# STM32LoRa.net
KiCad netlist of a schematic drawn in EAGLE
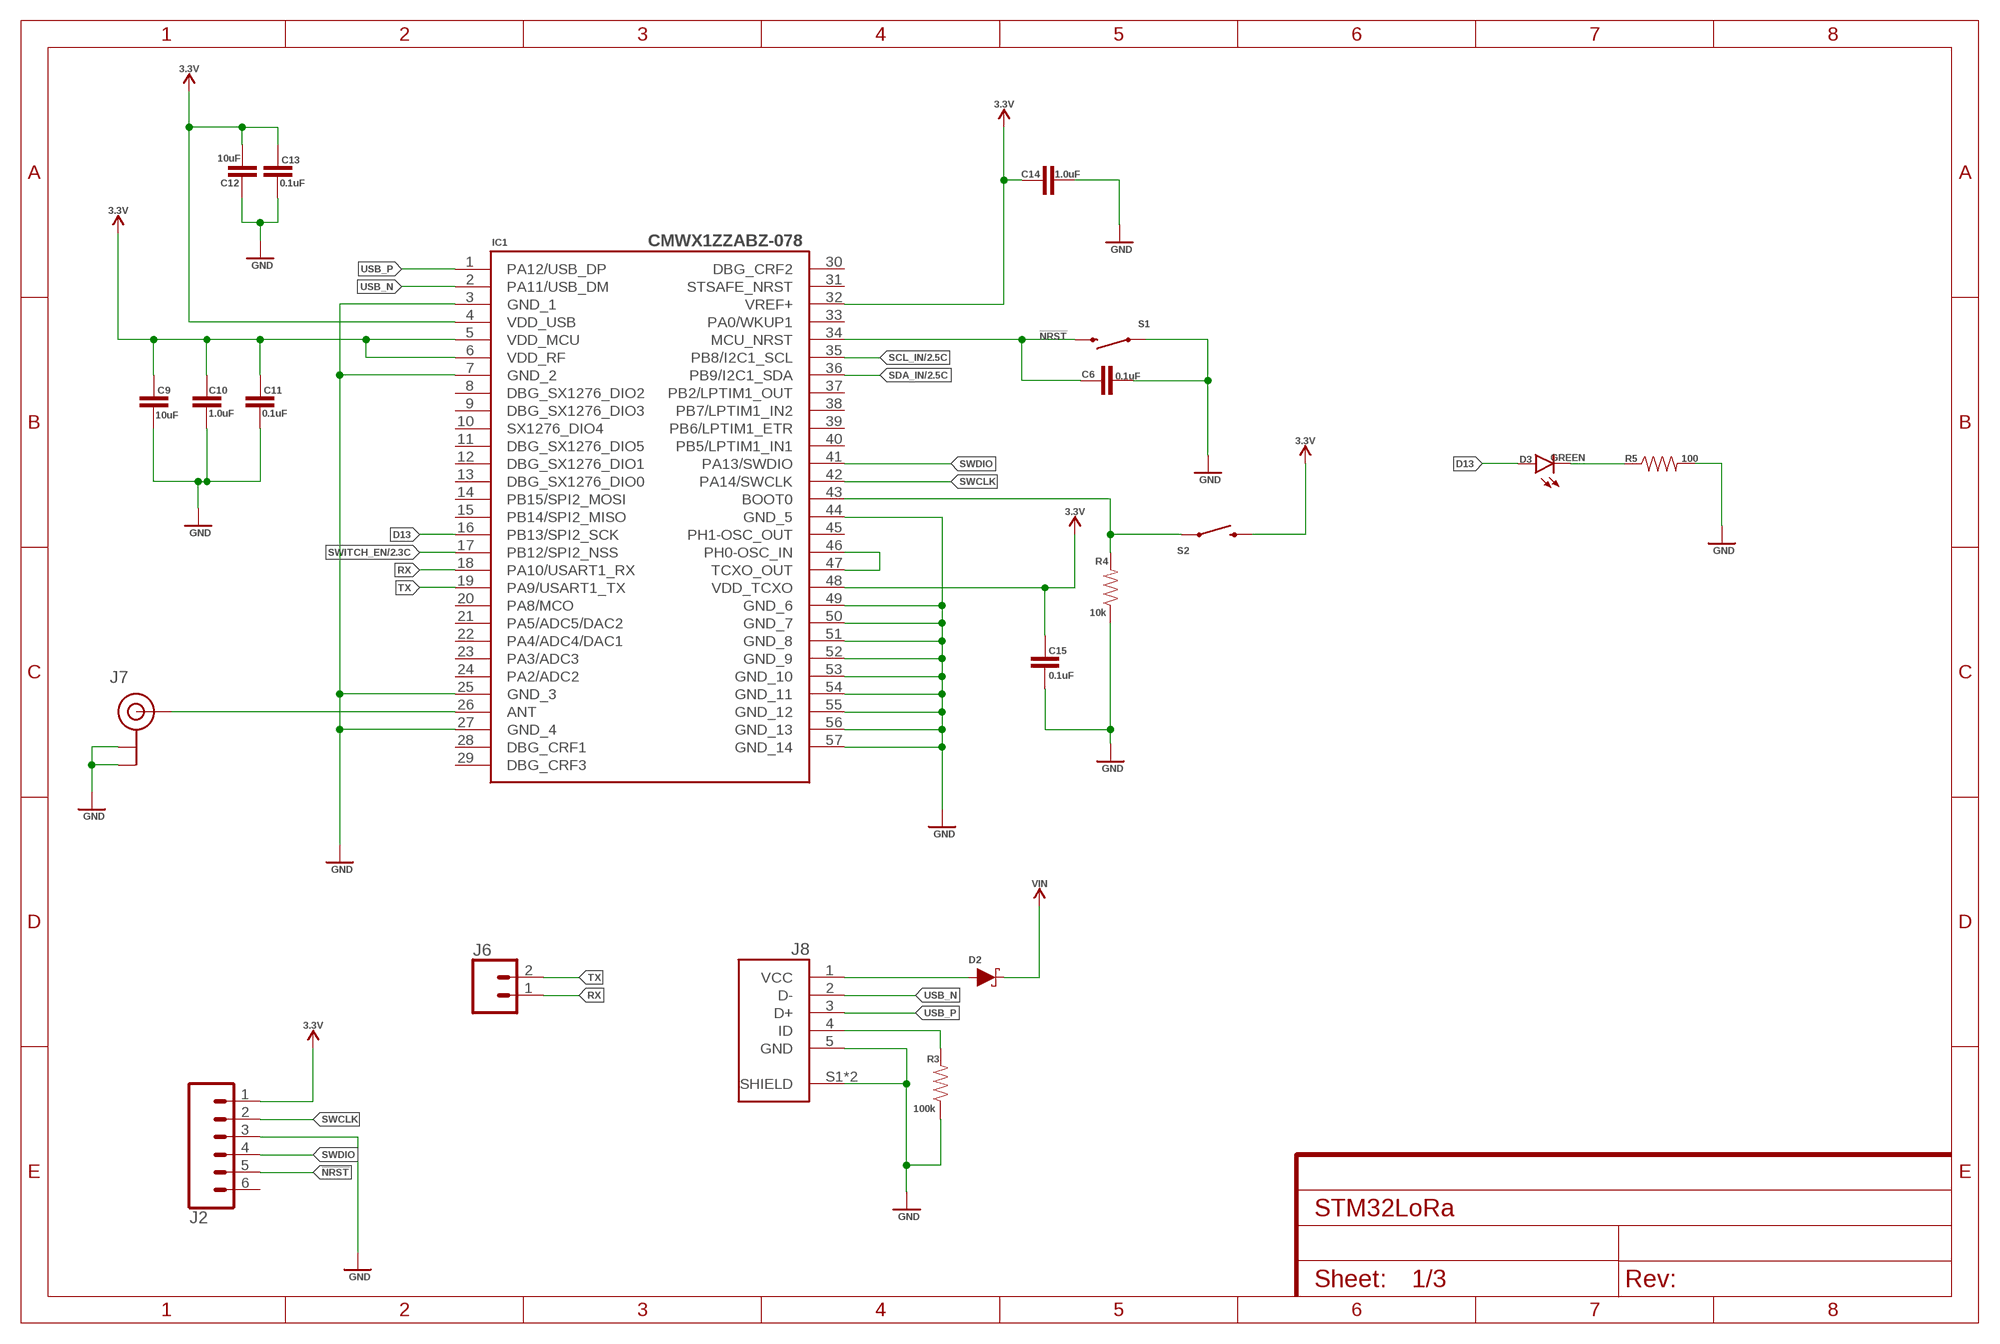
[diagram p0: schematic, sheet 1]
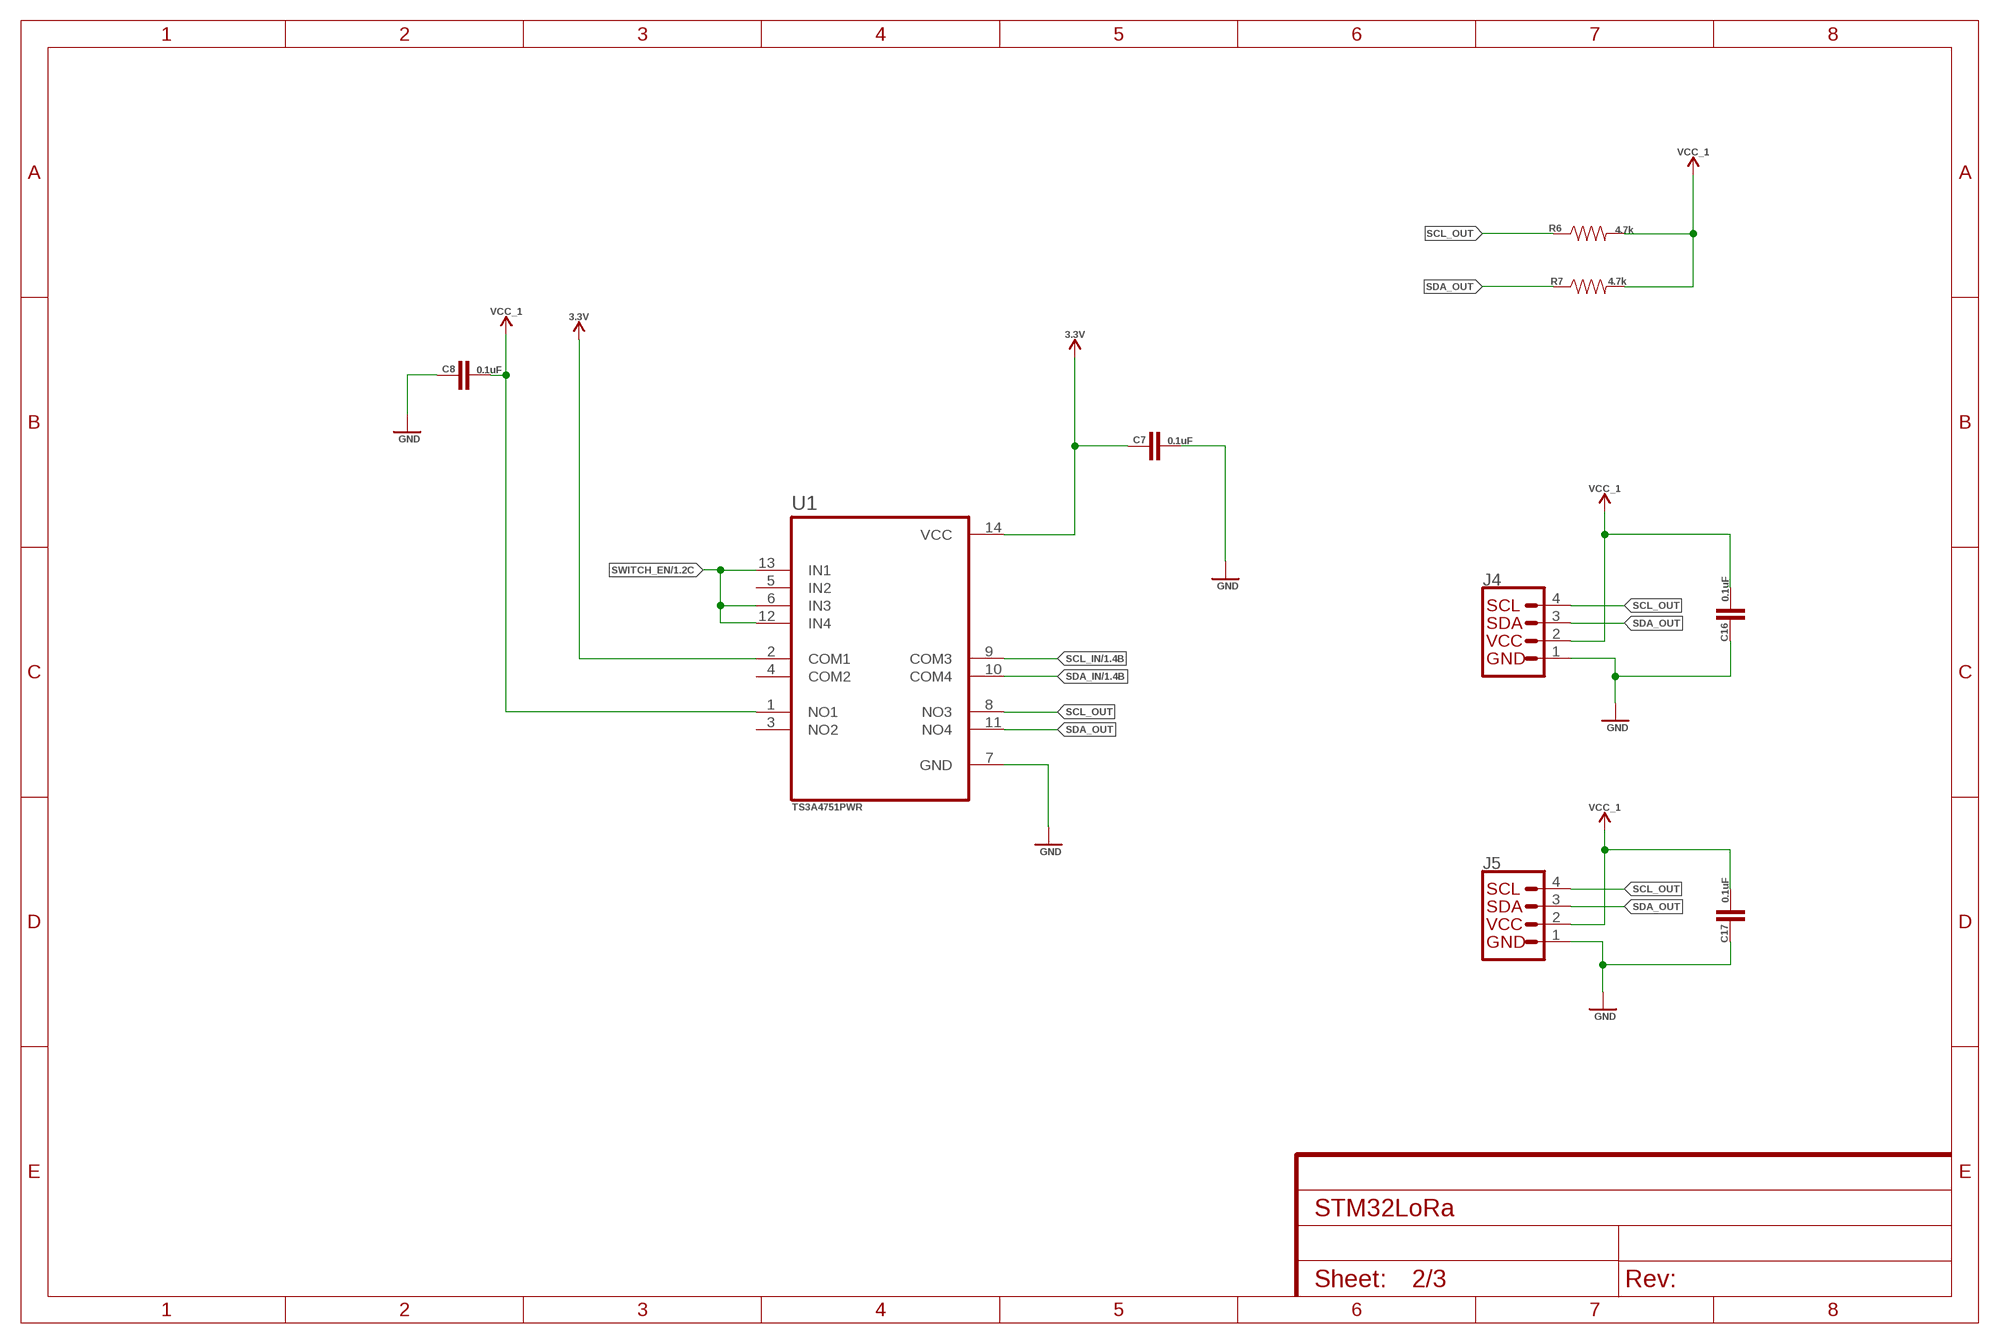
[diagram p1: schematic, sheet 2]
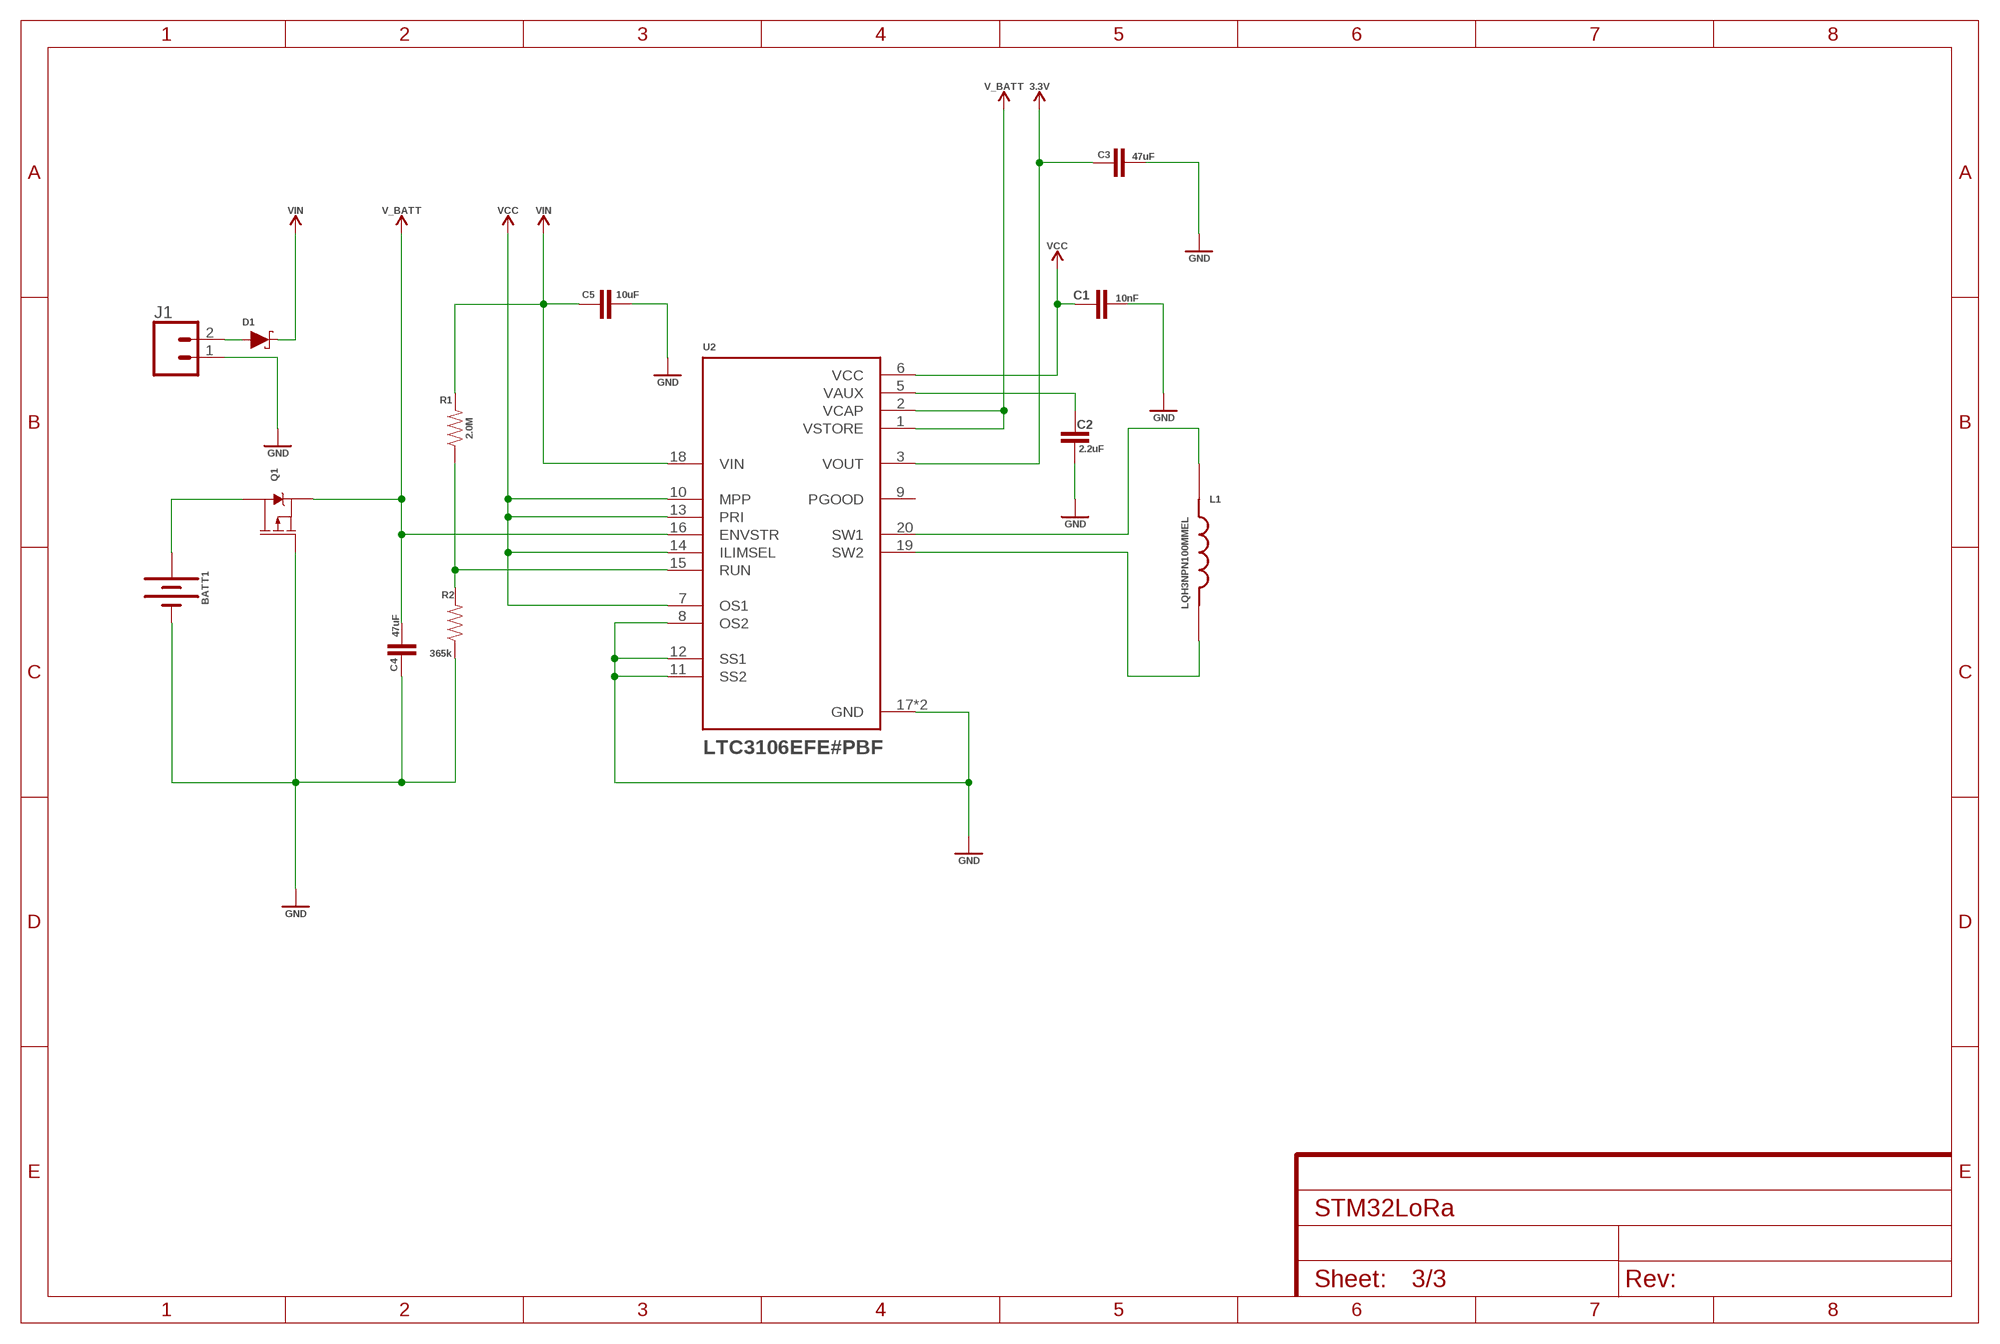
[diagram p2: schematic, sheet 3]

(export (version "E")
  (design (tool "Eeschema 10.0.6"))
  (components
    (comp (ref "C7")
      (value "0.1uF")
      (footprint "eagle-import:0603")
      (libsource (lib "eagle-import") (part "0.1UF-0603-25V-(+80/-20%)"))
    )
    (comp (ref "C8")
      (value "0.1uF")
      (footprint "eagle-import:0603")
      (libsource (lib "eagle-import") (part "0.1UF-0603-25V-(+80/-20%)"))
    )
    (comp (ref "C16")
      (value "0.1uF")
      (footprint "eagle-import:0603")
      (libsource (lib "eagle-import") (part "0.1UF-0603-25V-(+80/-20%)"))
    )
    (comp (ref "C17")
      (value "0.1uF")
      (footprint "eagle-import:0603")
      (libsource (lib "eagle-import") (part "0.1UF-0603-25V-(+80/-20%)"))
    )
    (comp (ref "J4")
      (value "Qwiic Right Angle")
      (footprint "eagle-import:1X04_1MM_RA")
      (libsource (lib "eagle-import") (part "I2C_STANDARDQWIIC"))
    )
    (comp (ref "J5")
      (value "I2C_STANDARD")
      (footprint "eagle-import:1X04")
      (libsource (lib "eagle-import") (part "I2C_STANDARD"))
    )
    (comp (ref "R6")
      (value "4.7k")
      (footprint "eagle-import:0603")
      (libsource (lib "eagle-import") (part "4.7KOHM-0603-1/10W-1%"))
    )
    (comp (ref "R7")
      (value "4.7k")
      (footprint "eagle-import:0603")
      (libsource (lib "eagle-import") (part "4.7KOHM-0603-1/10W-1%"))
    )
    (comp (ref "U1")
      (value "TS3A4751PWR")
      (footprint "eagle-import:SOP65P640X120-14N")
      (fields (field (name "DIGI-KEY_PART_NUMBER") "296-20700-1-ND") (field (name "MF") "Texas Instruments"))
      (libsource (lib "eagle-import") (part "TS3A4751PWR"))
    )
    (comp (ref "C6")
      (value "0.1uF")
      (footprint "eagle-import:0603")
      (libsource (lib "eagle-import") (part "0.1UF-0603-25V-(+80/-20%)"))
    )
    (comp (ref "C9")
      (value "10uF")
      (footprint "eagle-import:0603")
      (libsource (lib "eagle-import") (part "10UF-0603-6.3V-20%"))
    )
    (comp (ref "C10")
      (value "1.0uF")
      (footprint "eagle-import:0603")
      (libsource (lib "eagle-import") (part "1.0UF-0603-16V-10%"))
    )
    (comp (ref "C11")
      (value "0.1uF")
      (footprint "eagle-import:0603")
      (libsource (lib "eagle-import") (part "0.1UF-0603-25V-(+80/-20%)"))
    )
    (comp (ref "C12")
      (value "10uF")
      (footprint "eagle-import:0603")
      (libsource (lib "eagle-import") (part "10UF-0603-6.3V-20%"))
    )
    (comp (ref "C13")
      (value "0.1uF")
      (footprint "eagle-import:0603")
      (libsource (lib "eagle-import") (part "0.1UF-0603-25V-(+80/-20%)"))
    )
    (comp (ref "C14")
      (value "1.0uF")
      (footprint "eagle-import:0603")
      (libsource (lib "eagle-import") (part "1.0UF-0603-16V-10%"))
    )
    (comp (ref "C15")
      (value "0.1uF")
      (footprint "eagle-import:0603")
      (libsource (lib "eagle-import") (part "0.1UF-0603-25V-(+80/-20%)"))
    )
    (comp (ref "D2")
      (value "120mA/40V/370mV")
      (footprint "eagle-import:SOD-523")
      (libsource (lib "eagle-import") (part "DIODE-SCHOTTKY-RB751S40"))
    )
    (comp (ref "D3")
      (value "GREEN")
      (footprint "eagle-import:LED-0603")
      (libsource (lib "eagle-import") (part "LED-GREEN0603"))
    )
    (comp (ref "IC1")
      (value "CMWX1ZZABZ-078")
      (footprint "eagle-import:CMWX1ZZABZ-078")
      (fields (field (name "MOUSER_PART_NUMBER") "81-CMWX1ZZABZ-078"))
      (libsource (lib "eagle-import") (part "CMWX1ZZABZ-078"))
    )
    (comp (ref "J2")
      (value "CONN_06LONGPADS")
      (footprint "eagle-import:1X06_LONGPADS")
      (libsource (lib "eagle-import") (part "CONN_06LONGPADS"))
    )
    (comp (ref "J6")
      (value "CONN_02")
      (footprint "eagle-import:1X02")
      (libsource (lib "eagle-import") (part "CONN_02"))
    )
    (comp (ref "J7")
      (value "U.FL")
      (footprint "eagle-import:U.FL")
      (libsource (lib "eagle-import") (part "U.FL"))
    )
    (comp (ref "J8")
      (value "USB3131-30-0230-A_REVB")
      (footprint "eagle-import:GCT_USB3131-30-0230-A_REVB")
      (fields (field (name "MF") "Global Connector Technology") (field (name "MP") "USB3131-30-0230-A"))
      (libsource (lib "eagle-import") (part "USB3131-30-0230-A_REVB"))
    )
    (comp (ref "R3")
      (value "100k")
      (footprint "eagle-import:0603")
      (libsource (lib "eagle-import") (part "100KOHM-0603-1/10W-1%"))
    )
    (comp (ref "R4")
      (value "10k")
      (footprint "eagle-import:0603")
      (libsource (lib "eagle-import") (part "10KOHM-0603-1/10W-1%"))
    )
    (comp (ref "R5")
      (value "100")
      (footprint "eagle-import:0603")
      (libsource (lib "eagle-import") (part "100OHM-0603-1/4W-5%"))
    )
    (comp (ref "S1")
      (value "MOMENTARY-SWITCH-SPST-SMD-4.6X2.8MM")
      (footprint "eagle-import:TACTILE_SWITCH_SMD_4.6X2.8MM")
      (libsource (lib "eagle-import") (part "MOMENTARY-SWITCH-SPST-SMD-4.6X2.8MM"))
    )
    (comp (ref "S2")
      (value "MOMENTARY-SWITCH-SPST-SMD-4.6X2.8MM")
      (footprint "eagle-import:TACTILE_SWITCH_SMD_4.6X2.8MM")
      (libsource (lib "eagle-import") (part "MOMENTARY-SWITCH-SPST-SMD-4.6X2.8MM"))
    )
    (comp (ref "BATT1")
      (value "KEYSTONE_54KEYSTONE_2")
      (footprint "eagle-import:KEYSTONE_V2")
      (libsource (lib "eagle-import") (part "KEYSTONE_54KEYSTONE_2"))
    )
    (comp (ref "C1")
      (value "10nF")
      (footprint "eagle-import:0603")
      (libsource (lib "eagle-import") (part "10NF-0603-50V-10%"))
    )
    (comp (ref "C2")
      (value "2.2uF")
      (footprint "eagle-import:0603")
      (libsource (lib "eagle-import") (part "2.2UF-0603-10V-20%"))
    )
    (comp (ref "C3")
      (value "47uF")
      (footprint "eagle-import:0603")
      (libsource (lib "eagle-import") (part "4.7UF0603"))
    )
    (comp (ref "C4")
      (value "47uF")
      (footprint "eagle-import:0603")
      (libsource (lib "eagle-import") (part "4.7UF0603"))
    )
    (comp (ref "C5")
      (value "10uF")
      (footprint "eagle-import:0603")
      (libsource (lib "eagle-import") (part "10UF-0603-6.3V-20%"))
    )
    (comp (ref "D1")
      (value "120mA/40V/370mV")
      (footprint "eagle-import:SOD-523")
      (libsource (lib "eagle-import") (part "DIODE-SCHOTTKY-RB751S40"))
    )
    (comp (ref "J1")
      (value "CONN_023.5MM")
      (footprint "eagle-import:SCREWTERMINAL-3.5MM-2")
      (libsource (lib "eagle-import") (part "CONN_023.5MM"))
    )
    (comp (ref "L1")
      (value "LQH3NPN100MMEL")
      (footprint "eagle-import:IND_LQH3NPN100MMEL")
      (fields (field (name "DIGI-KEY_PART_NUMBER") "490-15945-1-ND") (field (name "MF") "Murata"))
      (libsource (lib "eagle-import") (part "LQH3NPN100MMEL"))
    )
    (comp (ref "Q1")
      (value "2.5A/30V/105mΩ")
      (footprint "eagle-import:SOT23-3")
      (libsource (lib "eagle-import") (part "MOSFET_PCH-DMG2307L"))
    )
    (comp (ref "R1")
      (value "2.0M")
      (footprint "eagle-import:0603")
      (libsource (lib "eagle-import") (part "2MOHMS-0603-1/10W-1%"))
    )
    (comp (ref "R2")
      (value "365k")
      (footprint "eagle-import:0603")
      (libsource (lib "eagle-import") (part "390KOHM-0603-1/10W-1%"))
    )
    (comp (ref "U2")
      (value "LTC3106EFE#PBF")
      (footprint "eagle-import:SOP65P640X120-21N")
      (fields (field (name "MF") "Analog Devices"))
      (libsource (lib "eagle-import") (part "LTC3106EFE#PBF"))
    )
  )
  (nets
    (net (code "1") (name "3.3V") (class "Default")
      (node (ref "C10") (pin "1") (pinfunction "1_1") (pintype "passive"))
      (node (ref "C11") (pin "1") (pinfunction "1_1") (pintype "passive"))
      (node (ref "C12") (pin "2") (pinfunction "2_2") (pintype "passive"))
      (node (ref "C13") (pin "1") (pinfunction "1_1") (pintype "passive"))
      (node (ref "C14") (pin "1") (pinfunction "1_1") (pintype "passive"))
      (node (ref "C15") (pin "2") (pinfunction "2_2") (pintype "passive"))
      (node (ref "C3") (pin "1") (pinfunction "1_1") (pintype "passive"))
      (node (ref "C7") (pin "1") (pinfunction "1_1") (pintype "passive"))
      (node (ref "C9") (pin "1") (pinfunction "1_1") (pintype "passive"))
      (node (ref "IC1") (pin "32") (pinfunction "VREF+_32") (pintype "bidirectional"))
      (node (ref "IC1") (pin "4") (pinfunction "VDD_USB_4") (pintype "bidirectional"))
      (node (ref "IC1") (pin "48") (pinfunction "VDD_TCXO_48") (pintype "bidirectional"))
      (node (ref "IC1") (pin "5") (pinfunction "VDD_MCU_5") (pintype "bidirectional"))
      (node (ref "IC1") (pin "6") (pinfunction "VDD_RF_6") (pintype "bidirectional"))
      (node (ref "J2") (pin "1") (pinfunction "1_1") (pintype "passive"))
      (node (ref "S2") (pin "3") (pinfunction "2_3") (pintype "passive"))
      (node (ref "S2") (pin "4") (pinfunction "2_4") (pintype "passive"))
      (node (ref "U1") (pin "14") (pinfunction "VCC_14") (pintype "power_in"))
      (node (ref "U1") (pin "2") (pinfunction "COM1_2") (pintype "bidirectional"))
      (node (ref "U2") (pin "3") (pinfunction "VOUT_3") (pintype "output"))
    )
    (net (code "2") (name "D13") (class "Default")
      (node (ref "D3") (pin "A") (pinfunction "A_A") (pintype "passive"))
      (node (ref "IC1") (pin "16") (pinfunction "PB13/SPI2_SCK_16") (pintype "bidirectional"))
    )
    (net (code "3") (name "GND") (class "Default")
      (node (ref "BATT1") (pin "P$4") (pinfunction "-_P$4") (pintype "power_in"))
      (node (ref "BATT1") (pin "P$5") (pinfunction "-_P$5") (pintype "power_in"))
      (node (ref "BATT1") (pin "P$6") (pinfunction "-_P$6") (pintype "power_in"))
      (node (ref "C1") (pin "2") (pinfunction "2_2") (pintype "passive"))
      (node (ref "C10") (pin "2") (pinfunction "2_2") (pintype "passive"))
      (node (ref "C11") (pin "2") (pinfunction "2_2") (pintype "passive"))
      (node (ref "C12") (pin "1") (pinfunction "1_1") (pintype "passive"))
      (node (ref "C13") (pin "2") (pinfunction "2_2") (pintype "passive"))
      (node (ref "C14") (pin "2") (pinfunction "2_2") (pintype "passive"))
      (node (ref "C15") (pin "1") (pinfunction "1_1") (pintype "passive"))
      (node (ref "C16") (pin "1") (pinfunction "1_1") (pintype "passive"))
      (node (ref "C17") (pin "1") (pinfunction "1_1") (pintype "passive"))
      (node (ref "C2") (pin "2") (pinfunction "2_2") (pintype "passive"))
      (node (ref "C3") (pin "2") (pinfunction "2_2") (pintype "passive"))
      (node (ref "C4") (pin "1") (pinfunction "1_1") (pintype "passive"))
      (node (ref "C5") (pin "2") (pinfunction "2_2") (pintype "passive"))
      (node (ref "C6") (pin "2") (pinfunction "2_2") (pintype "passive"))
      (node (ref "C7") (pin "2") (pinfunction "2_2") (pintype "passive"))
      (node (ref "C8") (pin "1") (pinfunction "1_1") (pintype "passive"))
      (node (ref "C9") (pin "2") (pinfunction "2_2") (pintype "passive"))
      (node (ref "IC1") (pin "25") (pinfunction "GND_3_25") (pintype "bidirectional"))
      (node (ref "IC1") (pin "27") (pinfunction "GND_4_27") (pintype "bidirectional"))
      (node (ref "IC1") (pin "3") (pinfunction "GND_1_3") (pintype "bidirectional"))
      (node (ref "IC1") (pin "44") (pinfunction "GND_5_44") (pintype "bidirectional"))
      (node (ref "IC1") (pin "49") (pinfunction "GND_6_49") (pintype "bidirectional"))
      (node (ref "IC1") (pin "50") (pinfunction "GND_7_50") (pintype "bidirectional"))
      (node (ref "IC1") (pin "51") (pinfunction "GND_8_51") (pintype "bidirectional"))
      (node (ref "IC1") (pin "52") (pinfunction "GND_9_52") (pintype "bidirectional"))
      (node (ref "IC1") (pin "53") (pinfunction "GND_10_53") (pintype "bidirectional"))
      (node (ref "IC1") (pin "54") (pinfunction "GND_11_54") (pintype "bidirectional"))
      (node (ref "IC1") (pin "55") (pinfunction "GND_12_55") (pintype "bidirectional"))
      (node (ref "IC1") (pin "56") (pinfunction "GND_13_56") (pintype "bidirectional"))
      (node (ref "IC1") (pin "57") (pinfunction "GND_14_57") (pintype "bidirectional"))
      (node (ref "IC1") (pin "7") (pinfunction "GND_2_7") (pintype "bidirectional"))
      (node (ref "J1") (pin "1") (pinfunction "1_1") (pintype "passive"))
      (node (ref "J2") (pin "3") (pinfunction "3_3") (pintype "passive"))
      (node (ref "J4") (pin "1") (pinfunction "1_1") (pintype "power_in"))
      (node (ref "J5") (pin "1") (pinfunction "1_1") (pintype "power_in"))
      (node (ref "J7") (pin "1") (pinfunction "GND_1") (pintype "bidirectional"))
      (node (ref "J7") (pin "2") (pinfunction "GND_2") (pintype "bidirectional"))
      (node (ref "J8") (pin "5") (pinfunction "GND_5") (pintype "power_in"))
      (node (ref "J8") (pin "S1") (pinfunction "SHIELD_S1") (pintype "passive"))
      (node (ref "J8") (pin "S2") (pinfunction "SHIELD_S2") (pintype "passive"))
      (node (ref "Q1") (pin "1") (pinfunction "G_1") (pintype "bidirectional"))
      (node (ref "R2") (pin "1") (pinfunction "1_1") (pintype "passive"))
      (node (ref "R3") (pin "1") (pinfunction "1_1") (pintype "passive"))
      (node (ref "R4") (pin "1") (pinfunction "1_1") (pintype "passive"))
      (node (ref "R5") (pin "2") (pinfunction "2_2") (pintype "passive"))
      (node (ref "S1") (pin "1") (pinfunction "1_1") (pintype "passive"))
      (node (ref "S1") (pin "2") (pinfunction "1_2") (pintype "passive"))
      (node (ref "U1") (pin "7") (pinfunction "GND_7") (pintype "power_in"))
      (node (ref "U2") (pin "11") (pinfunction "SS2_11") (pintype "input"))
      (node (ref "U2") (pin "12") (pinfunction "SS1_12") (pintype "input"))
      (node (ref "U2") (pin "17") (pinfunction "GND_17") (pintype "power_in"))
      (node (ref "U2") (pin "21") (pinfunction "GND_21") (pintype "power_in"))
      (node (ref "U2") (pin "8") (pinfunction "OS2_8") (pintype "input"))
    )
    (net (code "4") (name "Net-(D1-PadA)") (class "Default")
      (node (ref "D1") (pin "A") (pinfunction "A_A") (pintype "passive"))
      (node (ref "J1") (pin "2") (pinfunction "2_2") (pintype "passive"))
    )
    (net (code "5") (name "Net-(D3-PadC)") (class "Default")
      (node (ref "D3") (pin "C") (pinfunction "C_C") (pintype "passive"))
      (node (ref "R5") (pin "1") (pinfunction "1_1") (pintype "passive"))
    )
    (net (code "6") (name "Net-(IC1-ANT)") (class "Default")
      (node (ref "IC1") (pin "26") (pinfunction "ANT_26") (pintype "bidirectional"))
      (node (ref "J7") (pin "FEED") (pinfunction "SIGNAL_FEED") (pintype "bidirectional"))
    )
    (net (code "7") (name "Net-(IC1-BOOT0)") (class "Default")
      (node (ref "IC1") (pin "43") (pinfunction "BOOT0_43") (pintype "bidirectional"))
      (node (ref "R4") (pin "2") (pinfunction "2_2") (pintype "passive"))
      (node (ref "S2") (pin "1") (pinfunction "1_1") (pintype "passive"))
      (node (ref "S2") (pin "2") (pinfunction "1_2") (pintype "passive"))
    )
    (net (code "8") (name "Net-(IC1-PH0-OSC_IN)") (class "Default")
      (node (ref "IC1") (pin "46") (pinfunction "PH0-OSC_IN_46") (pintype "bidirectional"))
      (node (ref "IC1") (pin "47") (pinfunction "TCXO_OUT_47") (pintype "bidirectional"))
    )
    (net (code "9") (name "Net-(J8-ID)") (class "Default")
      (node (ref "J8") (pin "4") (pinfunction "ID_4") (pintype "bidirectional"))
      (node (ref "R3") (pin "2") (pinfunction "2_2") (pintype "passive"))
    )
    (net (code "10") (name "Net-(J8-VCC)") (class "Default")
      (node (ref "D2") (pin "A") (pinfunction "A_A") (pintype "passive"))
      (node (ref "J8") (pin "1") (pinfunction "VCC_1") (pintype "power_in"))
    )
    (net (code "11") (name "Net-(Q1-D)") (class "Default")
      (node (ref "BATT1") (pin "P$1") (pinfunction "+_P$1") (pintype "power_in"))
      (node (ref "BATT1") (pin "P$2") (pinfunction "+_P$2") (pintype "power_in"))
      (node (ref "BATT1") (pin "P$3") (pinfunction "+_P$3") (pintype "power_in"))
      (node (ref "Q1") (pin "3") (pinfunction "D_3") (pintype "bidirectional"))
    )
    (net (code "12") (name "Net-(U2-RUN)") (class "Default")
      (node (ref "R1") (pin "1") (pinfunction "1_1") (pintype "passive"))
      (node (ref "R2") (pin "2") (pinfunction "2_2") (pintype "passive"))
      (node (ref "U2") (pin "15") (pinfunction "RUN_15") (pintype "input"))
    )
    (net (code "13") (name "Net-(U2-SW1)") (class "Default")
      (node (ref "L1") (pin "1") (pinfunction "1_1") (pintype "passive"))
      (node (ref "U2") (pin "20") (pinfunction "SW1_20") (pintype "passive"))
    )
    (net (code "14") (name "Net-(U2-SW2)") (class "Default")
      (node (ref "L1") (pin "2") (pinfunction "2_2") (pintype "passive"))
      (node (ref "U2") (pin "19") (pinfunction "SW2_19") (pintype "passive"))
    )
    (net (code "15") (name "Net-(U2-VAUX)") (class "Default")
      (node (ref "C2") (pin "1") (pinfunction "1_1") (pintype "passive"))
      (node (ref "U2") (pin "5") (pinfunction "VAUX_5") (pintype "power_in"))
    )
    (net (code "16") (name "RX") (class "Default")
      (node (ref "IC1") (pin "18") (pinfunction "PA10/USART1_RX_18") (pintype "bidirectional"))
      (node (ref "J6") (pin "1") (pinfunction "1_1") (pintype "passive"))
    )
    (net (code "17") (name "SCL_IN") (class "Default")
      (node (ref "IC1") (pin "35") (pinfunction "PB8/I2C1_SCL_35") (pintype "bidirectional"))
      (node (ref "U1") (pin "9") (pinfunction "COM3_9") (pintype "bidirectional"))
    )
    (net (code "18") (name "SCL_OUT") (class "Default")
      (node (ref "J4") (pin "4") (pinfunction "4_4") (pintype "passive"))
      (node (ref "J5") (pin "4") (pinfunction "4_4") (pintype "passive"))
      (node (ref "R6") (pin "1") (pinfunction "1_1") (pintype "passive"))
      (node (ref "U1") (pin "8") (pinfunction "NO3_8") (pintype "bidirectional"))
    )
    (net (code "19") (name "SDA_IN") (class "Default")
      (node (ref "IC1") (pin "36") (pinfunction "PB9/I2C1_SDA_36") (pintype "bidirectional"))
      (node (ref "U1") (pin "10") (pinfunction "COM4_10") (pintype "bidirectional"))
    )
    (net (code "20") (name "SDA_OUT") (class "Default")
      (node (ref "J4") (pin "3") (pinfunction "3_3") (pintype "passive"))
      (node (ref "J5") (pin "3") (pinfunction "3_3") (pintype "passive"))
      (node (ref "R7") (pin "1") (pinfunction "1_1") (pintype "passive"))
      (node (ref "U1") (pin "11") (pinfunction "NO4_11") (pintype "bidirectional"))
    )
    (net (code "21") (name "SWCLK") (class "Default")
      (node (ref "IC1") (pin "42") (pinfunction "PA14/SWCLK_42") (pintype "bidirectional"))
      (node (ref "J2") (pin "2") (pinfunction "2_2") (pintype "passive"))
    )
    (net (code "22") (name "SWDIO") (class "Default")
      (node (ref "IC1") (pin "41") (pinfunction "PA13/SWDIO_41") (pintype "bidirectional"))
      (node (ref "J2") (pin "4") (pinfunction "4_4") (pintype "passive"))
    )
    (net (code "23") (name "SWITCH_EN") (class "Default")
      (node (ref "IC1") (pin "17") (pinfunction "PB12/SPI2_NSS_17") (pintype "bidirectional"))
      (node (ref "U1") (pin "12") (pinfunction "IN4_12") (pintype "input"))
      (node (ref "U1") (pin "13") (pinfunction "IN1_13") (pintype "input"))
      (node (ref "U1") (pin "6") (pinfunction "IN3_6") (pintype "input"))
    )
    (net (code "24") (name "TX") (class "Default")
      (node (ref "IC1") (pin "19") (pinfunction "PA9/USART1_TX_19") (pintype "bidirectional"))
      (node (ref "J6") (pin "2") (pinfunction "2_2") (pintype "passive"))
    )
    (net (code "25") (name "USB_N") (class "Default")
      (node (ref "IC1") (pin "2") (pinfunction "PA11/USB_DM_2") (pintype "bidirectional"))
      (node (ref "J8") (pin "2") (pinfunction "D-_2") (pintype "bidirectional"))
    )
    (net (code "26") (name "USB_P") (class "Default")
      (node (ref "IC1") (pin "1") (pinfunction "PA12/USB_DP_1") (pintype "bidirectional"))
      (node (ref "J8") (pin "3") (pinfunction "D+_3") (pintype "bidirectional"))
    )
    (net (code "27") (name "VCC") (class "Default")
      (node (ref "C1") (pin "1") (pinfunction "1_1") (pintype "passive"))
      (node (ref "U2") (pin "10") (pinfunction "MPP_10") (pintype "input"))
      (node (ref "U2") (pin "13") (pinfunction "PRI_13") (pintype "input"))
      (node (ref "U2") (pin "14") (pinfunction "ILIMSEL_14") (pintype "input"))
      (node (ref "U2") (pin "6") (pinfunction "VCC_6") (pintype "power_in"))
      (node (ref "U2") (pin "7") (pinfunction "OS1_7") (pintype "input"))
    )
    (net (code "28") (name "VCC_1") (class "Default")
      (node (ref "C16") (pin "2") (pinfunction "2_2") (pintype "passive"))
      (node (ref "C17") (pin "2") (pinfunction "2_2") (pintype "passive"))
      (node (ref "C8") (pin "2") (pinfunction "2_2") (pintype "passive"))
      (node (ref "J4") (pin "2") (pinfunction "2_2") (pintype "power_in"))
      (node (ref "J5") (pin "2") (pinfunction "2_2") (pintype "power_in"))
      (node (ref "R6") (pin "2") (pinfunction "2_2") (pintype "passive"))
      (node (ref "R7") (pin "2") (pinfunction "2_2") (pintype "passive"))
      (node (ref "U1") (pin "1") (pinfunction "NO1_1") (pintype "bidirectional"))
    )
    (net (code "29") (name "VIN") (class "Default")
      (node (ref "C5") (pin "1") (pinfunction "1_1") (pintype "passive"))
      (node (ref "D1") (pin "C") (pinfunction "C_C") (pintype "passive"))
      (node (ref "D2") (pin "C") (pinfunction "C_C") (pintype "passive"))
      (node (ref "R1") (pin "2") (pinfunction "2_2") (pintype "passive"))
      (node (ref "U2") (pin "18") (pinfunction "VIN_18") (pintype "input"))
    )
    (net (code "30") (name "V_BATT") (class "Default")
      (node (ref "C4") (pin "2") (pinfunction "2_2") (pintype "passive"))
      (node (ref "Q1") (pin "2") (pinfunction "S_2") (pintype "bidirectional"))
      (node (ref "U2") (pin "1") (pinfunction "VSTORE_1") (pintype "power_in"))
      (node (ref "U2") (pin "16") (pinfunction "ENVSTR_16") (pintype "input"))
      (node (ref "U2") (pin "2") (pinfunction "VCAP_2") (pintype "power_in"))
    )
    (net (code "31") (name "unconnected-(IC1-DBG_CRF1-Pad28)") (class "Default")
      (node (ref "IC1") (pin "28") (pinfunction "DBG_CRF1_28") (pintype "bidirectional"))
    )
    (net (code "32") (name "unconnected-(IC1-DBG_CRF2-Pad30)") (class "Default")
      (node (ref "IC1") (pin "30") (pinfunction "DBG_CRF2_30") (pintype "bidirectional"))
    )
    (net (code "33") (name "unconnected-(IC1-DBG_CRF3-Pad29)") (class "Default")
      (node (ref "IC1") (pin "29") (pinfunction "DBG_CRF3_29") (pintype "bidirectional"))
    )
    (net (code "34") (name "unconnected-(IC1-DBG_SX1276_DIO0-Pad13)") (class "Default")
      (node (ref "IC1") (pin "13") (pinfunction "DBG_SX1276_DIO0_13") (pintype "bidirectional"))
    )
    (net (code "35") (name "unconnected-(IC1-DBG_SX1276_DIO1-Pad12)") (class "Default")
      (node (ref "IC1") (pin "12") (pinfunction "DBG_SX1276_DIO1_12") (pintype "bidirectional"))
    )
    (net (code "36") (name "unconnected-(IC1-DBG_SX1276_DIO2-Pad8)") (class "Default")
      (node (ref "IC1") (pin "8") (pinfunction "DBG_SX1276_DIO2_8") (pintype "bidirectional"))
    )
    (net (code "37") (name "unconnected-(IC1-DBG_SX1276_DIO3-Pad9)") (class "Default")
      (node (ref "IC1") (pin "9") (pinfunction "DBG_SX1276_DIO3_9") (pintype "bidirectional"))
    )
    (net (code "38") (name "unconnected-(IC1-DBG_SX1276_DIO5-Pad11)") (class "Default")
      (node (ref "IC1") (pin "11") (pinfunction "DBG_SX1276_DIO5_11") (pintype "bidirectional"))
    )
    (net (code "39") (name "unconnected-(IC1-PA0{slash}WKUP1-Pad33)") (class "Default")
      (node (ref "IC1") (pin "33") (pinfunction "PA0/WKUP1_33") (pintype "bidirectional"))
    )
    (net (code "40") (name "unconnected-(IC1-PA2{slash}ADC2-Pad24)") (class "Default")
      (node (ref "IC1") (pin "24") (pinfunction "PA2/ADC2_24") (pintype "bidirectional"))
    )
    (net (code "41") (name "unconnected-(IC1-PA3{slash}ADC3-Pad23)") (class "Default")
      (node (ref "IC1") (pin "23") (pinfunction "PA3/ADC3_23") (pintype "bidirectional"))
    )
    (net (code "42") (name "unconnected-(IC1-PA4{slash}ADC4{slash}DAC1-Pad22)") (class "Default")
      (node (ref "IC1") (pin "22") (pinfunction "PA4/ADC4/DAC1_22") (pintype "bidirectional"))
    )
    (net (code "43") (name "unconnected-(IC1-PA5{slash}ADC5{slash}DAC2-Pad21)") (class "Default")
      (node (ref "IC1") (pin "21") (pinfunction "PA5/ADC5/DAC2_21") (pintype "bidirectional"))
    )
    (net (code "44") (name "unconnected-(IC1-PA8{slash}MCO-Pad20)") (class "Default")
      (node (ref "IC1") (pin "20") (pinfunction "PA8/MCO_20") (pintype "bidirectional"))
    )
    (net (code "45") (name "unconnected-(IC1-PB2{slash}LPTIM1_OUT-Pad37)") (class "Default")
      (node (ref "IC1") (pin "37") (pinfunction "PB2/LPTIM1_OUT_37") (pintype "bidirectional"))
    )
    (net (code "46") (name "unconnected-(IC1-PB5{slash}LPTIM1_IN1-Pad40)") (class "Default")
      (node (ref "IC1") (pin "40") (pinfunction "PB5/LPTIM1_IN1_40") (pintype "bidirectional"))
    )
    (net (code "47") (name "unconnected-(IC1-PB6{slash}LPTIM1_ETR-Pad39)") (class "Default")
      (node (ref "IC1") (pin "39") (pinfunction "PB6/LPTIM1_ETR_39") (pintype "bidirectional"))
    )
    (net (code "48") (name "unconnected-(IC1-PB7{slash}LPTIM1_IN2-Pad38)") (class "Default")
      (node (ref "IC1") (pin "38") (pinfunction "PB7/LPTIM1_IN2_38") (pintype "bidirectional"))
    )
    (net (code "49") (name "unconnected-(IC1-PB14{slash}SPI2_MISO-Pad15)") (class "Default")
      (node (ref "IC1") (pin "15") (pinfunction "PB14/SPI2_MISO_15") (pintype "bidirectional"))
    )
    (net (code "50") (name "unconnected-(IC1-PB15{slash}SPI2_MOSI-Pad14)") (class "Default")
      (node (ref "IC1") (pin "14") (pinfunction "PB15/SPI2_MOSI_14") (pintype "bidirectional"))
    )
    (net (code "51") (name "unconnected-(IC1-PH1-OSC_OUT-Pad45)") (class "Default")
      (node (ref "IC1") (pin "45") (pinfunction "PH1-OSC_OUT_45") (pintype "bidirectional"))
    )
    (net (code "52") (name "unconnected-(IC1-STSAFE_NRST-Pad31)") (class "Default")
      (node (ref "IC1") (pin "31") (pinfunction "STSAFE_NRST_31") (pintype "bidirectional"))
    )
    (net (code "53") (name "unconnected-(IC1-SX1276_DIO4-Pad10)") (class "Default")
      (node (ref "IC1") (pin "10") (pinfunction "SX1276_DIO4_10") (pintype "bidirectional"))
    )
    (net (code "54") (name "unconnected-(J2-Pad6)") (class "Default")
      (node (ref "J2") (pin "6") (pinfunction "6_6") (pintype "passive"))
    )
    (net (code "55") (name "unconnected-(U1-COM2-Pad4)") (class "Default")
      (node (ref "U1") (pin "4") (pinfunction "COM2_4") (pintype "bidirectional"))
    )
    (net (code "56") (name "unconnected-(U1-IN2-Pad5)") (class "Default")
      (node (ref "U1") (pin "5") (pinfunction "IN2_5") (pintype "input"))
    )
    (net (code "57") (name "unconnected-(U1-NO2-Pad3)") (class "Default")
      (node (ref "U1") (pin "3") (pinfunction "NO2_3") (pintype "bidirectional"))
    )
    (net (code "58") (name "unconnected-(U2-PGOOD-Pad9)") (class "Default")
      (node (ref "U2") (pin "9") (pinfunction "PGOOD_9") (pintype "output"))
    )
    (net (code "59") (name "~{NRST}") (class "Default")
      (node (ref "C6") (pin "1") (pinfunction "1_1") (pintype "passive"))
      (node (ref "IC1") (pin "34") (pinfunction "MCU_NRST_34") (pintype "bidirectional"))
      (node (ref "J2") (pin "5") (pinfunction "5_5") (pintype "passive"))
      (node (ref "S1") (pin "3") (pinfunction "2_3") (pintype "passive"))
      (node (ref "S1") (pin "4") (pinfunction "2_4") (pintype "passive"))
    )
  )
)
